# skydrop.net
KiCad netlist of a schematic drawn in EAGLE
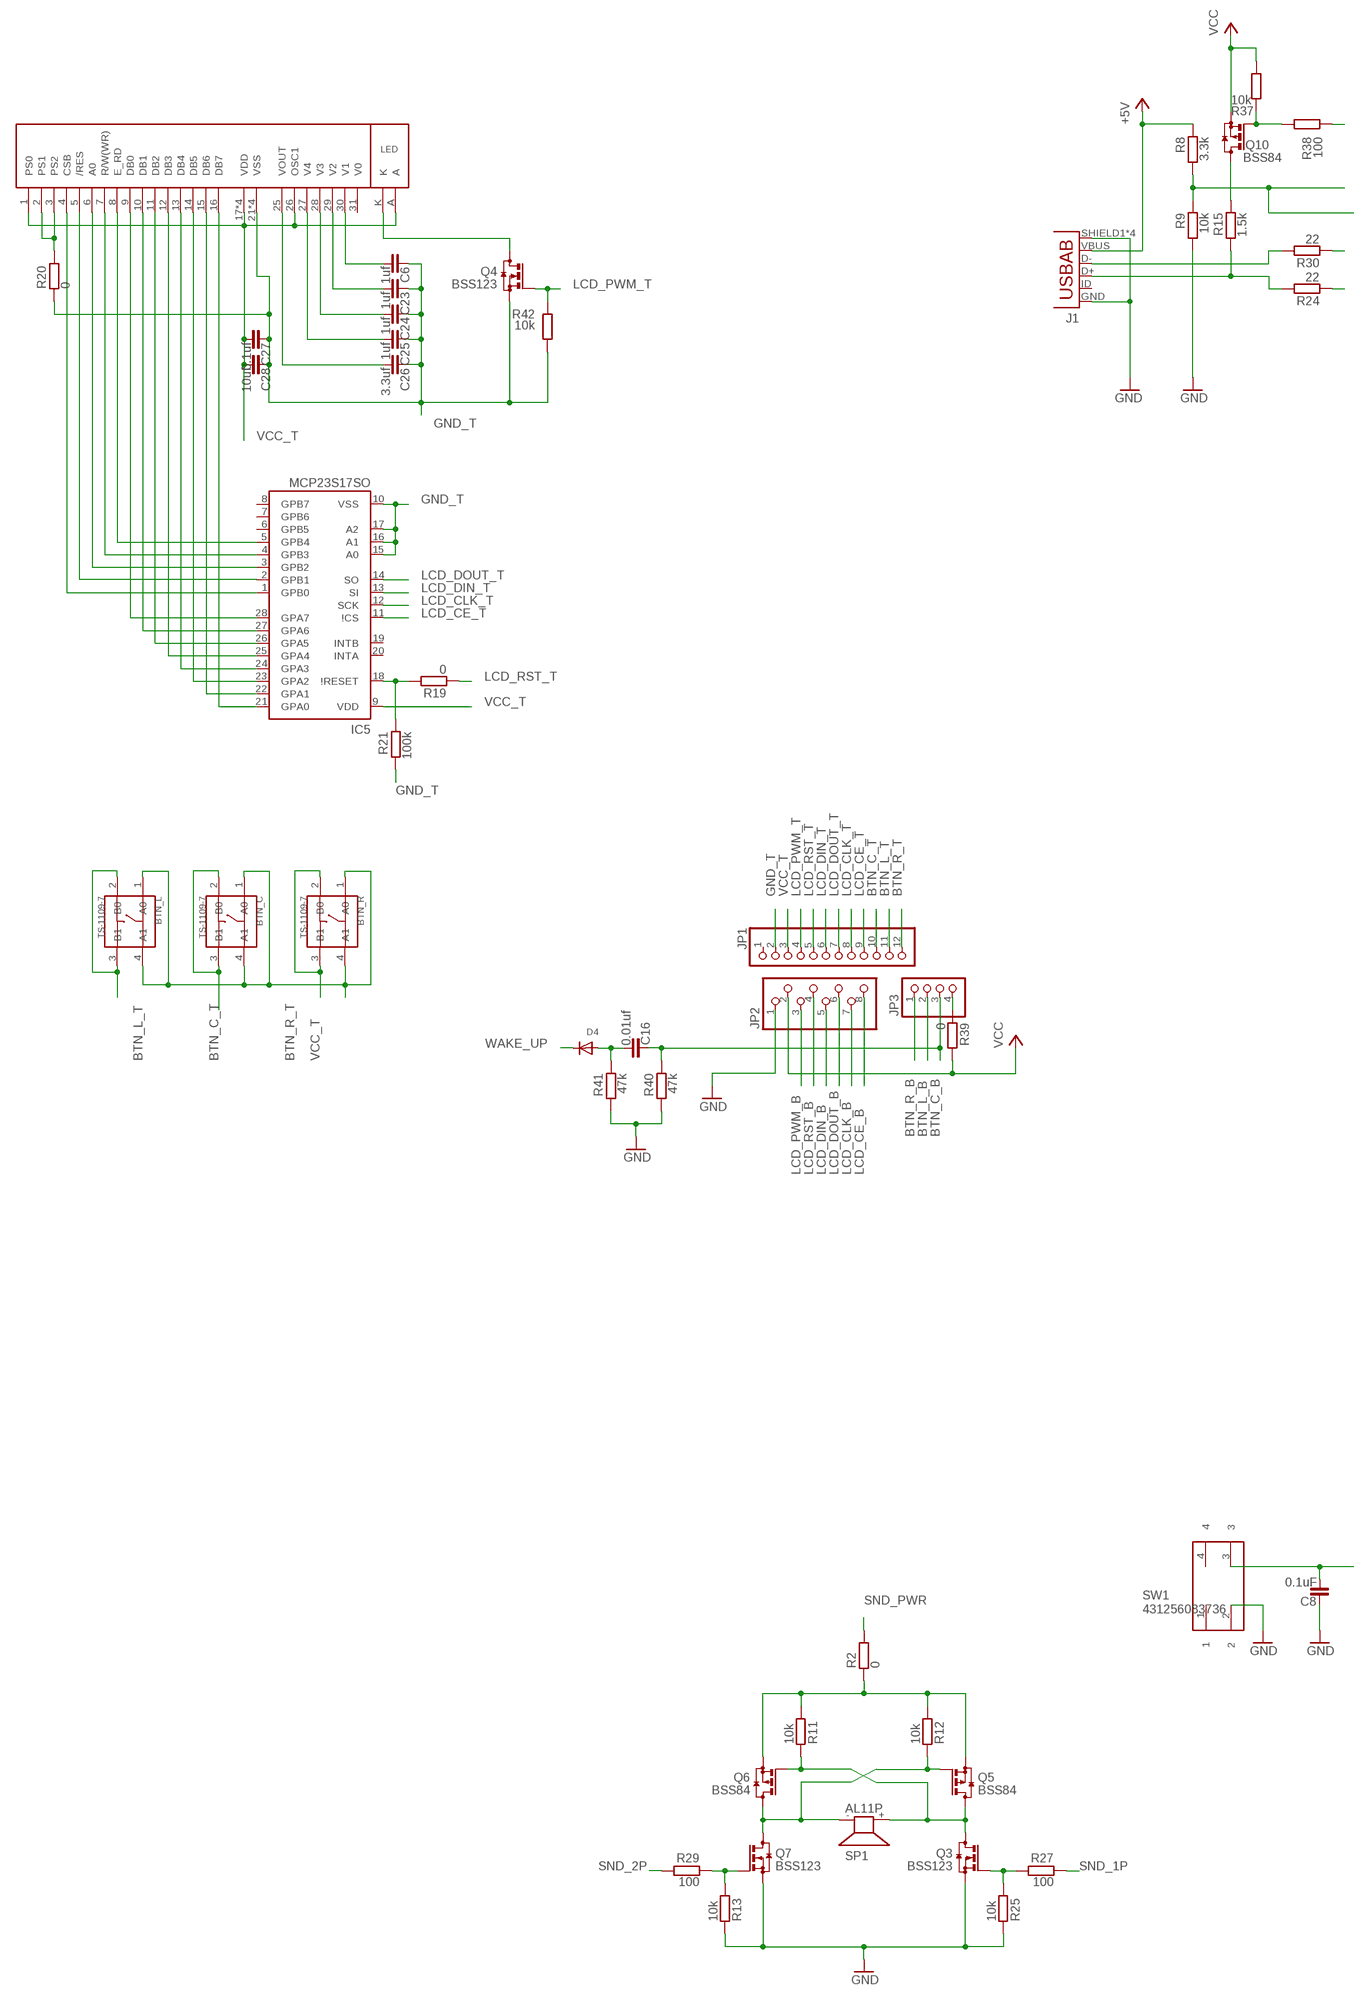
[diagram p0: schematic, sheet 1, part 1 of 2]
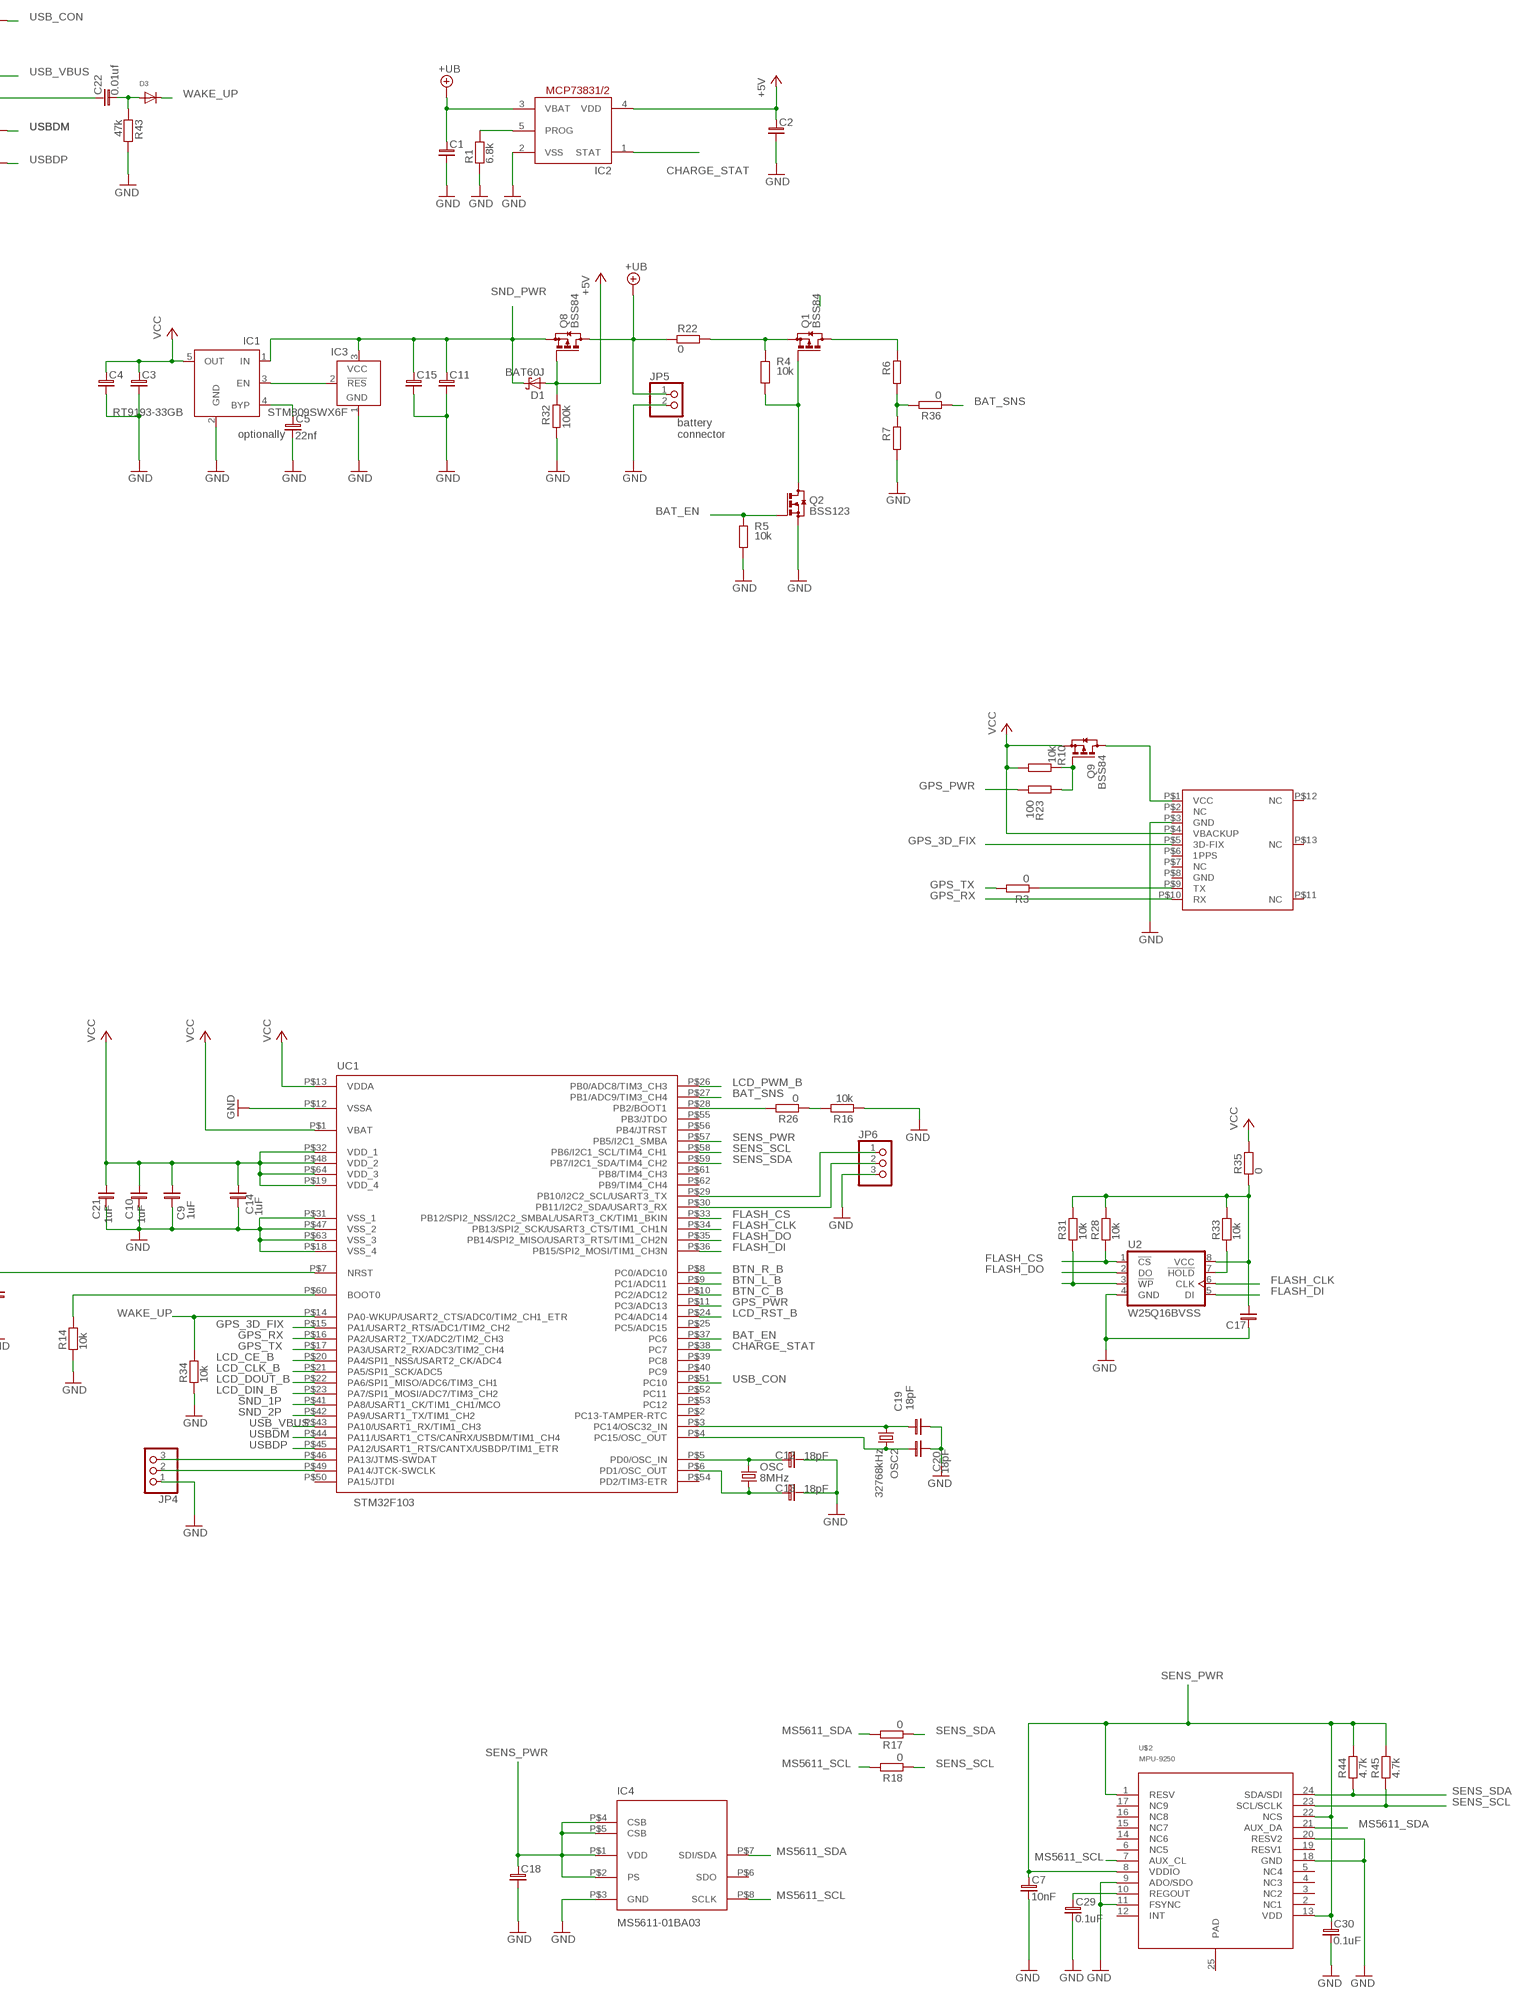
[diagram p1: schematic, sheet 1, part 2 of 2]

(export (version "E")
  (design (tool "Eeschema 10.0.6"))
  (components
    (comp (ref "BTN_C")
      (value "TS-1109-7")
      (footprint "eagle-import:SW4-6.2X6.2X5.0MM")
      (libsource (lib "eagle-import") (part "DIP-BUTTON-TOP-BLACK(4P-D6.2MM)"))
    )
    (comp (ref "BTN_L")
      (value "TS-1109-7")
      (footprint "eagle-import:SW4-6.2X6.2X5.0MM")
      (libsource (lib "eagle-import") (part "DIP-BUTTON-TOP-BLACK(4P-D6.2MM)"))
    )
    (comp (ref "BTN_R")
      (value "TS-1109-7")
      (footprint "eagle-import:SW4-6.2X6.2X5.0MM")
      (libsource (lib "eagle-import") (part "DIP-BUTTON-TOP-BLACK(4P-D6.2MM)"))
    )
    (comp (ref "C1")
      (value "C_0805")
      (footprint "eagle-import:C0805")
      (libsource (lib "eagle-import") (part "C_0805"))
    )
    (comp (ref "C2")
      (value "C_0805")
      (footprint "eagle-import:C0805")
      (libsource (lib "eagle-import") (part "C_0805"))
    )
    (comp (ref "C3")
      (value "C_0805")
      (footprint "eagle-import:C0805")
      (libsource (lib "eagle-import") (part "C_0805"))
    )
    (comp (ref "C4")
      (value "C_0805")
      (footprint "eagle-import:C0805")
      (libsource (lib "eagle-import") (part "C_0805"))
    )
    (comp (ref "C5")
      (value "22nf")
      (footprint "eagle-import:C0805")
      (libsource (lib "eagle-import") (part "C_0805"))
    )
    (comp (ref "C6")
      (value "1uf")
      (footprint "eagle-import:C0805")
      (libsource (lib "eagle-import") (part "C_0805"))
    )
    (comp (ref "C7")
      (value "10nF")
      (footprint "eagle-import:C0805")
      (libsource (lib "eagle-import") (part "C_0805"))
    )
    (comp (ref "C8")
      (value "0.1uF")
      (footprint "eagle-import:C0805")
      (libsource (lib "eagle-import") (part "C_0805"))
    )
    (comp (ref "C9")
      (value "1uF")
      (footprint "eagle-import:C0805")
      (libsource (lib "eagle-import") (part "C_0805"))
    )
    (comp (ref "C10")
      (value "1uF")
      (footprint "eagle-import:C0805")
      (libsource (lib "eagle-import") (part "C_0805"))
    )
    (comp (ref "C11")
      (value "C_0805")
      (footprint "eagle-import:C0805")
      (libsource (lib "eagle-import") (part "C_0805"))
    )
    (comp (ref "C12")
      (value "18pF")
      (footprint "eagle-import:C0805")
      (libsource (lib "eagle-import") (part "C_0805"))
    )
    (comp (ref "C13")
      (value "18pF")
      (footprint "eagle-import:C0805")
      (libsource (lib "eagle-import") (part "C_0805"))
    )
    (comp (ref "C14")
      (value "1uF")
      (footprint "eagle-import:C0805")
      (libsource (lib "eagle-import") (part "C_0805"))
    )
    (comp (ref "C15")
      (value "C_0805")
      (footprint "eagle-import:C0805")
      (libsource (lib "eagle-import") (part "C_0805"))
    )
    (comp (ref "C16")
      (value "0.01uf")
      (footprint "eagle-import:C0805")
      (libsource (lib "eagle-import") (part "C_0805"))
    )
    (comp (ref "C17")
      (value "C_0805")
      (footprint "eagle-import:C0805")
      (libsource (lib "eagle-import") (part "C_0805"))
    )
    (comp (ref "C18")
      (value "C_0805")
      (footprint "eagle-import:C0805")
      (libsource (lib "eagle-import") (part "C_0805"))
    )
    (comp (ref "C19")
      (value "18pF")
      (footprint "eagle-import:C0805")
      (libsource (lib "eagle-import") (part "C_0805"))
    )
    (comp (ref "C20")
      (value "18pF")
      (footprint "eagle-import:C0805")
      (libsource (lib "eagle-import") (part "C_0805"))
    )
    (comp (ref "C21")
      (value "1uF")
      (footprint "eagle-import:C0805")
      (libsource (lib "eagle-import") (part "C_0805"))
    )
    (comp (ref "C22")
      (value "0.01uf")
      (footprint "eagle-import:C0805")
      (libsource (lib "eagle-import") (part "C_0805"))
    )
    (comp (ref "C23")
      (value "1uf")
      (footprint "eagle-import:C0805")
      (libsource (lib "eagle-import") (part "C_0805"))
    )
    (comp (ref "C24")
      (value "1uf")
      (footprint "eagle-import:C0805")
      (libsource (lib "eagle-import") (part "C_0805"))
    )
    (comp (ref "C25")
      (value "1uf")
      (footprint "eagle-import:C0805")
      (libsource (lib "eagle-import") (part "C_0805"))
    )
    (comp (ref "C26")
      (value "3.3uf")
      (footprint "eagle-import:C0805")
      (libsource (lib "eagle-import") (part "C_0805"))
    )
    (comp (ref "C27")
      (value "0.1uf")
      (footprint "eagle-import:C0805")
      (libsource (lib "eagle-import") (part "C_0805"))
    )
    (comp (ref "C28")
      (value "10uf")
      (footprint "eagle-import:C0805")
      (libsource (lib "eagle-import") (part "C_0805"))
    )
    (comp (ref "C29")
      (value "0.1uF")
      (footprint "eagle-import:C0805")
      (libsource (lib "eagle-import") (part "C_0805"))
    )
    (comp (ref "C30")
      (value "0.1uF")
      (footprint "eagle-import:C0805")
      (libsource (lib "eagle-import") (part "C_0805"))
    )
    (comp (ref "D1")
      (value "BAT60J")
      (footprint "eagle-import:SOD323_ST")
      (libsource (lib "eagle-import") (part "BAT60J"))
    )
    (comp (ref "D3")
      (value "DIODE_SOD-123FL")
      (footprint "eagle-import:SOD-123FL")
      (libsource (lib "eagle-import") (part "DIODE_SOD-123FL"))
    )
    (comp (ref "D4")
      (value "DIODE_SOD-123FL")
      (footprint "eagle-import:SOD-123FL")
      (libsource (lib "eagle-import") (part "DIODE_SOD-123FL"))
    )
    (comp (ref "IC1")
      (value "RT9193-33GB")
      (footprint "eagle-import:SOT23-5")
      (libsource (lib "eagle-import") (part "MIC5219XX"))
    )
    (comp (ref "IC2")
      (value "MCP73831/OT")
      (footprint "eagle-import:SOT23-5L")
      (libsource (lib "eagle-import") (part "MCP73831/OT"))
    )
    (comp (ref "IC3")
      (value "STM809SWX6F")
      (footprint "eagle-import:SOT23B-3")
      (fields (field (name "MF") "MICROCHIP") (field (name "MPN") "TCM809MENB713"))
      (libsource (lib "eagle-import") (part "TCM809"))
    )
    (comp (ref "IC4")
      (value "MS5611-01BA03")
      (footprint "eagle-import:MS5611-01BA03")
      (libsource (lib "eagle-import") (part "MS5611-01BA03"))
    )
    (comp (ref "IC5")
      (value "MCP23S17SO")
      (footprint "eagle-import:SO28W")
      (libsource (lib "eagle-import") (part "MCP23S17SO"))
    )
    (comp (ref "J1")
      (value "USB-AB")
      (footprint "eagle-import:USB-AB-MICRO-SMD")
      (libsource (lib "eagle-import") (part "USB-AB"))
    )
    (comp (ref "JP1")
      (value "PINHD-1X12")
      (footprint "eagle-import:1X12")
      (libsource (lib "eagle-import") (part "PINHD-1X12"))
    )
    (comp (ref "JP2")
      (value "PINHD-1X8")
      (footprint "eagle-import:1X08")
      (libsource (lib "eagle-import") (part "PINHD-1X8"))
    )
    (comp (ref "JP3")
      (value "PINHD-1X4")
      (footprint "eagle-import:1X04")
      (libsource (lib "eagle-import") (part "PINHD-1X4"))
    )
    (comp (ref "JP4")
      (value "PINHD-1X3")
      (footprint "eagle-import:1X03")
      (libsource (lib "eagle-import") (part "PINHD-1X3"))
    )
    (comp (ref "JP5")
      (value "PINHD-1X2")
      (footprint "eagle-import:1X02")
      (libsource (lib "eagle-import") (part "PINHD-1X2"))
    )
    (comp (ref "JP6")
      (value "PINHD-1X3")
      (footprint "eagle-import:1X03")
      (libsource (lib "eagle-import") (part "PINHD-1X3"))
    )
    (comp (ref "OSC")
      (value "8MHz")
      (footprint "eagle-import:HC49_S")
      (libsource (lib "eagle-import") (part "CRYSTALHC49S"))
    )
    (comp (ref "OSC2")
      (value "32768kHz")
      (footprint "eagle-import:MM20SS")
      (libsource (lib "eagle-import") (part "CRYSTALMM20SS"))
    )
    (comp (ref "Q1")
      (value "BSS84")
      (footprint "eagle-import:SOT23")
      (libsource (lib "eagle-import") (part "BSS84"))
    )
    (comp (ref "Q2")
      (value "BSS123")
      (footprint "eagle-import:SOT23")
      (libsource (lib "eagle-import") (part "BSS123"))
    )
    (comp (ref "Q3")
      (value "BSS123")
      (footprint "eagle-import:SOT23")
      (libsource (lib "eagle-import") (part "BSS123"))
    )
    (comp (ref "Q4")
      (value "BSS123")
      (footprint "eagle-import:SOT23")
      (libsource (lib "eagle-import") (part "BSS123"))
    )
    (comp (ref "Q5")
      (value "BSS84")
      (footprint "eagle-import:SOT23")
      (libsource (lib "eagle-import") (part "BSS84"))
    )
    (comp (ref "Q6")
      (value "BSS84")
      (footprint "eagle-import:SOT23")
      (libsource (lib "eagle-import") (part "BSS84"))
    )
    (comp (ref "Q7")
      (value "BSS123")
      (footprint "eagle-import:SOT23")
      (libsource (lib "eagle-import") (part "BSS123"))
    )
    (comp (ref "Q8")
      (value "BSS84")
      (footprint "eagle-import:SOT23")
      (libsource (lib "eagle-import") (part "BSS84"))
    )
    (comp (ref "Q9")
      (value "BSS84")
      (footprint "eagle-import:SOT23")
      (libsource (lib "eagle-import") (part "BSS84"))
    )
    (comp (ref "Q10")
      (value "BSS84")
      (footprint "eagle-import:SOT23")
      (libsource (lib "eagle-import") (part "BSS84"))
    )
    (comp (ref "R1")
      (value "6.8k")
      (footprint "eagle-import:R0805")
      (libsource (lib "eagle-import") (part "R_0805"))
    )
    (comp (ref "R2")
      (value "0")
      (footprint "eagle-import:R1206")
      (libsource (lib "eagle-import") (part "R_1206"))
    )
    (comp (ref "R3")
      (value "0")
      (footprint "eagle-import:R1206")
      (libsource (lib "eagle-import") (part "R_1206"))
    )
    (comp (ref "R4")
      (value "10k")
      (footprint "eagle-import:R0805")
      (libsource (lib "eagle-import") (part "R_0805"))
    )
    (comp (ref "R5")
      (value "10k")
      (footprint "eagle-import:R0805")
      (libsource (lib "eagle-import") (part "R_0805"))
    )
    (comp (ref "R6")
      (value "R_0805")
      (footprint "eagle-import:R0805")
      (libsource (lib "eagle-import") (part "R_0805"))
    )
    (comp (ref "R7")
      (value "R_0805")
      (footprint "eagle-import:R0805")
      (libsource (lib "eagle-import") (part "R_0805"))
    )
    (comp (ref "R8")
      (value "3.3k")
      (footprint "eagle-import:R0805")
      (libsource (lib "eagle-import") (part "R_0805"))
    )
    (comp (ref "R9")
      (value "10k")
      (footprint "eagle-import:R0805")
      (libsource (lib "eagle-import") (part "R_0805"))
    )
    (comp (ref "R10")
      (value "10k")
      (footprint "eagle-import:R0805")
      (libsource (lib "eagle-import") (part "R_0805"))
    )
    (comp (ref "R11")
      (value "10k")
      (footprint "eagle-import:R0805")
      (libsource (lib "eagle-import") (part "R_0805"))
    )
    (comp (ref "R12")
      (value "10k")
      (footprint "eagle-import:R0805")
      (libsource (lib "eagle-import") (part "R_0805"))
    )
    (comp (ref "R13")
      (value "10k")
      (footprint "eagle-import:R0805")
      (libsource (lib "eagle-import") (part "R_0805"))
    )
    (comp (ref "R14")
      (value "10k")
      (footprint "eagle-import:R0805")
      (libsource (lib "eagle-import") (part "R_0805"))
    )
    (comp (ref "R15")
      (value "1.5k")
      (footprint "eagle-import:R0805")
      (libsource (lib "eagle-import") (part "R_0805"))
    )
    (comp (ref "R16")
      (value "10k")
      (footprint "eagle-import:R0805")
      (libsource (lib "eagle-import") (part "R_0805"))
    )
    (comp (ref "R17")
      (value "0")
      (footprint "eagle-import:R1206")
      (libsource (lib "eagle-import") (part "R_1206"))
    )
    (comp (ref "R18")
      (value "0")
      (footprint "eagle-import:R1206")
      (libsource (lib "eagle-import") (part "R_1206"))
    )
    (comp (ref "R19")
      (value "0")
      (footprint "eagle-import:R1206")
      (libsource (lib "eagle-import") (part "R_1206"))
    )
    (comp (ref "R20")
      (value "0")
      (footprint "eagle-import:R1206")
      (libsource (lib "eagle-import") (part "R_1206"))
    )
    (comp (ref "R21")
      (value "100k")
      (footprint "eagle-import:R0805")
      (libsource (lib "eagle-import") (part "R_0805"))
    )
    (comp (ref "R22")
      (value "0")
      (footprint "eagle-import:R1206")
      (libsource (lib "eagle-import") (part "R_1206"))
    )
    (comp (ref "R23")
      (value "100")
      (footprint "eagle-import:R0805")
      (libsource (lib "eagle-import") (part "R_0805"))
    )
    (comp (ref "R24")
      (value "22")
      (footprint "eagle-import:R0805")
      (libsource (lib "eagle-import") (part "R_0805"))
    )
    (comp (ref "R25")
      (value "10k")
      (footprint "eagle-import:R0805")
      (libsource (lib "eagle-import") (part "R_0805"))
    )
    (comp (ref "R26")
      (value "0")
      (footprint "eagle-import:R1206")
      (libsource (lib "eagle-import") (part "R_1206"))
    )
    (comp (ref "R27")
      (value "100")
      (footprint "eagle-import:R0805")
      (libsource (lib "eagle-import") (part "R_0805"))
    )
    (comp (ref "R28")
      (value "10k")
      (footprint "eagle-import:R0805")
      (libsource (lib "eagle-import") (part "R_0805"))
    )
    (comp (ref "R29")
      (value "100")
      (footprint "eagle-import:R0805")
      (libsource (lib "eagle-import") (part "R_0805"))
    )
    (comp (ref "R30")
      (value "22")
      (footprint "eagle-import:R0805")
      (libsource (lib "eagle-import") (part "R_0805"))
    )
    (comp (ref "R31")
      (value "10k")
      (footprint "eagle-import:R0805")
      (libsource (lib "eagle-import") (part "R_0805"))
    )
    (comp (ref "R32")
      (value "100k")
      (footprint "eagle-import:R0805")
      (libsource (lib "eagle-import") (part "R_0805"))
    )
    (comp (ref "R33")
      (value "10k")
      (footprint "eagle-import:R0805")
      (libsource (lib "eagle-import") (part "R_0805"))
    )
    (comp (ref "R34")
      (value "10k")
      (footprint "eagle-import:R0805")
      (libsource (lib "eagle-import") (part "R_0805"))
    )
    (comp (ref "R35")
      (value "0")
      (footprint "eagle-import:R1206")
      (libsource (lib "eagle-import") (part "R_1206"))
    )
    (comp (ref "R36")
      (value "0")
      (footprint "eagle-import:R1206")
      (libsource (lib "eagle-import") (part "R_1206"))
    )
    (comp (ref "R37")
      (value "10k")
      (footprint "eagle-import:R0805")
      (libsource (lib "eagle-import") (part "R_0805"))
    )
    (comp (ref "R38")
      (value "100")
      (footprint "eagle-import:R0805")
      (libsource (lib "eagle-import") (part "R_0805"))
    )
    (comp (ref "R39")
      (value "0")
      (footprint "eagle-import:R1206")
      (libsource (lib "eagle-import") (part "R_1206"))
    )
    (comp (ref "R40")
      (value "47k")
      (footprint "eagle-import:R0805")
      (libsource (lib "eagle-import") (part "R_0805"))
    )
    (comp (ref "R41")
      (value "47k")
      (footprint "eagle-import:R0805")
      (libsource (lib "eagle-import") (part "R_0805"))
    )
    (comp (ref "R42")
      (value "10k")
      (footprint "eagle-import:R0805")
      (libsource (lib "eagle-import") (part "R_0805"))
    )
    (comp (ref "R43")
      (value "47k")
      (footprint "eagle-import:R0805")
      (libsource (lib "eagle-import") (part "R_0805"))
    )
    (comp (ref "R44")
      (value "4.7k")
      (footprint "eagle-import:R0805")
      (libsource (lib "eagle-import") (part "R_0805"))
    )
    (comp (ref "R45")
      (value "4.7k")
      (footprint "eagle-import:R0805")
      (libsource (lib "eagle-import") (part "R_0805"))
    )
    (comp (ref "SP1")
      (value "AL11P")
      (footprint "eagle-import:AL11P")
      (libsource (lib "eagle-import") (part "AL11P"))
    )
    (comp (ref "SW1")
      (value "431256083736")
      (footprint "eagle-import:431256083736")
      (libsource (lib "eagle-import") (part "431256083736"))
    )
    (comp (ref "U$1")
      (value "NOKIA5110")
      (footprint "eagle-import:NOKIA5110")
      (libsource (lib "eagle-import") (part "NOKIA5110"))
    )
    (comp (ref "U$2")
      (value "MPU-9250")
      (footprint "eagle-import:LEAD-QFN24")
      (libsource (lib "eagle-import") (part "MPU-9250"))
    )
    (comp (ref "U1")
      (value "GPS_FGPMMOPA6C")
      (footprint "eagle-import:FGPMMOPA6C")
      (libsource (lib "eagle-import") (part "GPS_FGPMMOPA6C"))
    )
    (comp (ref "U2")
      (value "W25Q16BVSS")
      (footprint "eagle-import:SO08-SS")
      (libsource (lib "eagle-import") (part "W25Q16BVSS"))
    )
    (comp (ref "UC1")
      (value "STM32F103")
      (footprint "eagle-import:TQFP-10X10-64")
      (libsource (lib "eagle-import") (part "STM32F103"))
    )
  )
  (nets
    (net (code "1") (name "+5V") (class "Default")
      (node (ref "C2") (pin "1") (pinfunction "1_1") (pintype "passive"))
      (node (ref "D1") (pin "A") (pinfunction "A_A") (pintype "passive"))
      (node (ref "IC2") (pin "4") (pinfunction "VDD_4") (pintype "power_in"))
      (node (ref "J1") (pin "VBUS") (pinfunction "VBUS_VBUS") (pintype "bidirectional"))
      (node (ref "Q8") (pin "1") (pinfunction "G_1") (pintype "passive"))
      (node (ref "R32") (pin "1") (pinfunction "1_1") (pintype "passive"))
      (node (ref "R8") (pin "1") (pinfunction "1_1") (pintype "passive"))
    )
    (net (code "2") (name "+UB") (class "Default")
      (node (ref "C1") (pin "1") (pinfunction "1_1") (pintype "passive"))
      (node (ref "IC2") (pin "3") (pinfunction "VBAT_3") (pintype "bidirectional"))
      (node (ref "JP5") (pin "1") (pinfunction "1_1") (pintype "passive"))
      (node (ref "Q8") (pin "3") (pinfunction "D_3") (pintype "passive"))
      (node (ref "R22") (pin "1") (pinfunction "1_1") (pintype "passive"))
    )
    (net (code "3") (name "/BAT_EN") (class "Default")
      (node (ref "Q2") (pin "1") (pinfunction "G_1") (pintype "passive"))
      (node (ref "R5") (pin "1") (pinfunction "1_1") (pintype "passive"))
      (node (ref "UC1") (pin "P$37") (pinfunction "PC6_P$37") (pintype "bidirectional"))
    )
    (net (code "4") (name "/BAT_SNS") (class "Default")
      (node (ref "R36") (pin "1") (pinfunction "1_1") (pintype "passive"))
      (node (ref "UC1") (pin "P$27") (pinfunction "PB1/ADC9/TIM3_CH4_P$27") (pintype "bidirectional"))
    )
    (net (code "5") (name "/BTN_C_B") (class "Default")
      (node (ref "C16") (pin "1") (pinfunction "1_1") (pintype "passive"))
      (node (ref "JP3") (pin "3") (pinfunction "3_3") (pintype "passive"))
      (node (ref "R40") (pin "1") (pinfunction "1_1") (pintype "passive"))
      (node (ref "UC1") (pin "P$10") (pinfunction "PC2/ADC12_P$10") (pintype "bidirectional"))
    )
    (net (code "6") (name "/BTN_C_T") (class "Default")
      (node (ref "BTN_C") (pin "2") (pinfunction "B0_2") (pintype "bidirectional"))
      (node (ref "BTN_C") (pin "3") (pinfunction "B1_3") (pintype "bidirectional"))
      (node (ref "JP1") (pin "10") (pinfunction "10_10") (pintype "passive"))
    )
    (net (code "7") (name "/BTN_L_B") (class "Default")
      (node (ref "JP3") (pin "2") (pinfunction "2_2") (pintype "passive"))
      (node (ref "UC1") (pin "P$9") (pinfunction "PC1/ADC11_P$9") (pintype "bidirectional"))
    )
    (net (code "8") (name "/BTN_L_T") (class "Default")
      (node (ref "BTN_L") (pin "2") (pinfunction "B0_2") (pintype "bidirectional"))
      (node (ref "BTN_L") (pin "3") (pinfunction "B1_3") (pintype "bidirectional"))
      (node (ref "JP1") (pin "11") (pinfunction "11_11") (pintype "passive"))
    )
    (net (code "9") (name "/BTN_R_B") (class "Default")
      (node (ref "JP3") (pin "1") (pinfunction "1_1") (pintype "passive"))
      (node (ref "UC1") (pin "P$8") (pinfunction "PC0/ADC10_P$8") (pintype "bidirectional"))
    )
    (net (code "10") (name "/BTN_R_T") (class "Default")
      (node (ref "BTN_R") (pin "2") (pinfunction "B0_2") (pintype "bidirectional"))
      (node (ref "BTN_R") (pin "3") (pinfunction "B1_3") (pintype "bidirectional"))
      (node (ref "JP1") (pin "12") (pinfunction "12_12") (pintype "passive"))
    )
    (net (code "11") (name "/CHARGE_STAT") (class "Default")
      (node (ref "IC2") (pin "1") (pinfunction "STAT_1") (pintype "output"))
      (node (ref "UC1") (pin "P$38") (pinfunction "PC7_P$38") (pintype "bidirectional"))
    )
    (net (code "12") (name "/FLASH_CLK") (class "Default")
      (node (ref "U2") (pin "6") (pinfunction "CLK_6") (pintype "input"))
      (node (ref "UC1") (pin "P$34") (pinfunction "PB13/SPI2_SCK/USART3_CTS/TIM1_CH1N_P$34") (pintype "bidirectional"))
    )
    (net (code "13") (name "/FLASH_CS") (class "Default")
      (node (ref "R28") (pin "1") (pinfunction "1_1") (pintype "passive"))
      (node (ref "U2") (pin "1") (pinfunction "~{CS}_1") (pintype "input"))
      (node (ref "UC1") (pin "P$33") (pinfunction "PB12/SPI2_NSS/I2C2_SMBAL/USART3_CK/TIM1_BKIN_P$33") (pintype "bidirectional"))
    )
    (net (code "14") (name "/FLASH_DI") (class "Default")
      (node (ref "U2") (pin "5") (pinfunction "DI_5") (pintype "input"))
      (node (ref "UC1") (pin "P$36") (pinfunction "PB15/SPI2_MOSI/TIM1_CH3N_P$36") (pintype "bidirectional"))
    )
    (net (code "15") (name "/FLASH_DO") (class "Default")
      (node (ref "U2") (pin "2") (pinfunction "DO_2") (pintype "output"))
      (node (ref "UC1") (pin "P$35") (pinfunction "PB14/SPI2_MISO/USART3_RTS/TIM1_CH2N_P$35") (pintype "bidirectional"))
    )
    (net (code "16") (name "/GND_T") (class "Default")
      (node (ref "C23") (pin "1") (pinfunction "1_1") (pintype "passive"))
      (node (ref "C24") (pin "1") (pinfunction "1_1") (pintype "passive"))
      (node (ref "C25") (pin "1") (pinfunction "1_1") (pintype "passive"))
      (node (ref "C26") (pin "1") (pinfunction "1_1") (pintype "passive"))
      (node (ref "C27") (pin "1") (pinfunction "1_1") (pintype "passive"))
      (node (ref "C28") (pin "1") (pinfunction "1_1") (pintype "passive"))
      (node (ref "C6") (pin "1") (pinfunction "1_1") (pintype "passive"))
      (node (ref "IC5") (pin "10") (pinfunction "VSS_10") (pintype "power_in"))
      (node (ref "IC5") (pin "15") (pinfunction "A0_15") (pintype "input"))
      (node (ref "IC5") (pin "16") (pinfunction "A1_16") (pintype "input"))
      (node (ref "IC5") (pin "17") (pinfunction "A2_17") (pintype "input"))
      (node (ref "JP1") (pin "2") (pinfunction "2_2") (pintype "passive"))
      (node (ref "Q4") (pin "2") (pinfunction "S_2") (pintype "passive"))
      (node (ref "R20") (pin "1") (pinfunction "1_1") (pintype "passive"))
      (node (ref "R21") (pin "2") (pinfunction "2_2") (pintype "passive"))
      (node (ref "R42") (pin "2") (pinfunction "2_2") (pintype "passive"))
      (node (ref "U$1") (pin "21") (pinfunction "VSS_21") (pintype "bidirectional"))
      (node (ref "U$1") (pin "22") (pinfunction "VSS_22") (pintype "bidirectional"))
      (node (ref "U$1") (pin "23") (pinfunction "VSS_23") (pintype "bidirectional"))
      (node (ref "U$1") (pin "24") (pinfunction "VSS_24") (pintype "bidirectional"))
    )
    (net (code "17") (name "/GPS_3D_FIX") (class "Default")
      (node (ref "U1") (pin "P$5") (pinfunction "3D-FIX_P$5") (pintype "bidirectional"))
      (node (ref "UC1") (pin "P$15") (pinfunction "PA1/USART2_RTS/ADC1/TIM2_CH2_P$15") (pintype "bidirectional"))
    )
    (net (code "18") (name "/GPS_PWR") (class "Default")
      (node (ref "R23") (pin "2") (pinfunction "2_2") (pintype "passive"))
      (node (ref "UC1") (pin "P$11") (pinfunction "PC3/ADC13_P$11") (pintype "bidirectional"))
    )
    (net (code "19") (name "/GPS_RX") (class "Default")
      (node (ref "U1") (pin "P$10") (pinfunction "RX_P$10") (pintype "bidirectional"))
      (node (ref "UC1") (pin "P$16") (pinfunction "PA2/USART2_TX/ADC2/TIM2_CH3_P$16") (pintype "bidirectional"))
    )
    (net (code "20") (name "/GPS_TX") (class "Default")
      (node (ref "R3") (pin "2") (pinfunction "2_2") (pintype "passive"))
      (node (ref "UC1") (pin "P$17") (pinfunction "PA3/USART2_RX/ADC3/TIM2_CH4_P$17") (pintype "bidirectional"))
    )
    (net (code "21") (name "/LCD_CE_B") (class "Default")
      (node (ref "JP2") (pin "8") (pinfunction "8_8") (pintype "passive"))
      (node (ref "UC1") (pin "P$20") (pinfunction "PA4/SPI1_NSS/USART2_CK/ADC4_P$20") (pintype "bidirectional"))
    )
    (net (code "22") (name "/LCD_CE_T") (class "Default")
      (node (ref "IC5") (pin "11") (pinfunction "\\~{CS}_11") (pintype "input"))
      (node (ref "JP1") (pin "9") (pinfunction "9_9") (pintype "passive"))
    )
    (net (code "23") (name "/LCD_CLK_B") (class "Default")
      (node (ref "JP2") (pin "7") (pinfunction "7_7") (pintype "passive"))
      (node (ref "UC1") (pin "P$21") (pinfunction "PA5/SPI1_SCK/ADC5_P$21") (pintype "bidirectional"))
    )
    (net (code "24") (name "/LCD_CLK_T") (class "Default")
      (node (ref "IC5") (pin "12") (pinfunction "SCK_12") (pintype "input"))
      (node (ref "JP1") (pin "8") (pinfunction "8_8") (pintype "passive"))
    )
    (net (code "25") (name "/LCD_DIN_B") (class "Default")
      (node (ref "JP2") (pin "5") (pinfunction "5_5") (pintype "passive"))
      (node (ref "UC1") (pin "P$23") (pinfunction "PA7/SPI1_MOSI/ADC7/TIM3_CH2_P$23") (pintype "bidirectional"))
    )
    (net (code "26") (name "/LCD_DIN_T") (class "Default")
      (node (ref "IC5") (pin "13") (pinfunction "SI_13") (pintype "input"))
      (node (ref "JP1") (pin "6") (pinfunction "6_6") (pintype "passive"))
    )
    (net (code "27") (name "/LCD_DOUT_B") (class "Default")
      (node (ref "JP2") (pin "6") (pinfunction "6_6") (pintype "passive"))
      (node (ref "UC1") (pin "P$22") (pinfunction "PA6/SPI1_MISO/ADC6/TIM3_CH1_P$22") (pintype "bidirectional"))
    )
    (net (code "28") (name "/LCD_DOUT_T") (class "Default")
      (node (ref "IC5") (pin "14") (pinfunction "SO_14") (pintype "output"))
      (node (ref "JP1") (pin "7") (pinfunction "7_7") (pintype "passive"))
    )
    (net (code "29") (name "/LCD_PWM_B") (class "Default")
      (node (ref "JP2") (pin "3") (pinfunction "3_3") (pintype "passive"))
      (node (ref "UC1") (pin "P$26") (pinfunction "PB0/ADC8/TIM3_CH3_P$26") (pintype "bidirectional"))
    )
    (net (code "30") (name "/LCD_PWM_T") (class "Default")
      (node (ref "JP1") (pin "4") (pinfunction "4_4") (pintype "passive"))
      (node (ref "Q4") (pin "1") (pinfunction "G_1") (pintype "passive"))
      (node (ref "R42") (pin "1") (pinfunction "1_1") (pintype "passive"))
    )
    (net (code "31") (name "/LCD_RST_B") (class "Default")
      (node (ref "JP2") (pin "4") (pinfunction "4_4") (pintype "passive"))
      (node (ref "UC1") (pin "P$24") (pinfunction "PC4/ADC14_P$24") (pintype "bidirectional"))
    )
    (net (code "32") (name "/LCD_RST_T") (class "Default")
      (node (ref "JP1") (pin "5") (pinfunction "5_5") (pintype "passive"))
      (node (ref "R19") (pin "1") (pinfunction "1_1") (pintype "passive"))
    )
    (net (code "33") (name "/MS5611_SCL") (class "Default")
      (node (ref "IC4") (pin "P$8") (pinfunction "SCLK_P$8") (pintype "input"))
      (node (ref "R18") (pin "2") (pinfunction "2_2") (pintype "passive"))
      (node (ref "U$2") (pin "7") (pinfunction "AUX_CL_7") (pintype "bidirectional"))
    )
    (net (code "34") (name "/MS5611_SDA") (class "Default")
      (node (ref "IC4") (pin "P$7") (pinfunction "SDI/SDA_P$7") (pintype "bidirectional"))
      (node (ref "R17") (pin "2") (pinfunction "2_2") (pintype "passive"))
      (node (ref "U$2") (pin "21") (pinfunction "AUX_DA_21") (pintype "bidirectional"))
    )
    (net (code "35") (name "/SENS_PWR") (class "Default")
      (node (ref "C18") (pin "1") (pinfunction "1_1") (pintype "passive"))
      (node (ref "C30") (pin "1") (pinfunction "1_1") (pintype "passive"))
      (node (ref "C7") (pin "1") (pinfunction "1_1") (pintype "passive"))
      (node (ref "IC4") (pin "P$1") (pinfunction "VDD_P$1") (pintype "power_in"))
      (node (ref "IC4") (pin "P$2") (pinfunction "PS_P$2") (pintype "input"))
      (node (ref "IC4") (pin "P$4") (pinfunction "CSB_P$4") (pintype "input"))
      (node (ref "IC4") (pin "P$5") (pinfunction "CSB_P$5") (pintype "input"))
      (node (ref "R44") (pin "2") (pinfunction "2_2") (pintype "passive"))
      (node (ref "R45") (pin "2") (pinfunction "2_2") (pintype "passive"))
      (node (ref "U$2") (pin "1") (pinfunction "RESV_1") (pintype "bidirectional"))
      (node (ref "U$2") (pin "13") (pinfunction "VDD_13") (pintype "bidirectional"))
      (node (ref "U$2") (pin "22") (pinfunction "NCS_22") (pintype "bidirectional"))
      (node (ref "U$2") (pin "8") (pinfunction "VDDIO_8") (pintype "bidirectional"))
      (node (ref "UC1") (pin "P$57") (pinfunction "PB5/I2C1_SMBA_P$57") (pintype "bidirectional"))
    )
    (net (code "36") (name "/SENS_SCL") (class "Default")
      (node (ref "R18") (pin "1") (pinfunction "1_1") (pintype "passive"))
      (node (ref "R45") (pin "1") (pinfunction "1_1") (pintype "passive"))
      (node (ref "U$2") (pin "23") (pinfunction "SCL/SCLK_23") (pintype "bidirectional"))
      (node (ref "UC1") (pin "P$58") (pinfunction "PB6/I2C1_SCL/TIM4_CH1_P$58") (pintype "bidirectional"))
    )
    (net (code "37") (name "/SENS_SDA") (class "Default")
      (node (ref "R17") (pin "1") (pinfunction "1_1") (pintype "passive"))
      (node (ref "R44") (pin "1") (pinfunction "1_1") (pintype "passive"))
      (node (ref "U$2") (pin "24") (pinfunction "SDA/SDI_24") (pintype "bidirectional"))
      (node (ref "UC1") (pin "P$59") (pinfunction "PB7/I2C1_SDA/TIM4_CH2_P$59") (pintype "bidirectional"))
    )
    (net (code "38") (name "/SND_1P") (class "Default")
      (node (ref "R27") (pin "1") (pinfunction "1_1") (pintype "passive"))
      (node (ref "UC1") (pin "P$41") (pinfunction "PA8/USART1_CK/TIM1_CH1/MCO_P$41") (pintype "bidirectional"))
    )
    (net (code "39") (name "/SND_2P") (class "Default")
      (node (ref "R29") (pin "2") (pinfunction "2_2") (pintype "passive"))
      (node (ref "UC1") (pin "P$42") (pinfunction "PA9/USART1_TX/TIM1_CH2_P$42") (pintype "bidirectional"))
    )
    (net (code "40") (name "/SND_PWR") (class "Default")
      (node (ref "C11") (pin "1") (pinfunction "1_1") (pintype "passive"))
      (node (ref "C15") (pin "1") (pinfunction "1_1") (pintype "passive"))
      (node (ref "D1") (pin "C") (pinfunction "C_C") (pintype "passive"))
      (node (ref "IC1") (pin "1") (pinfunction "IN_1") (pintype "input"))
      (node (ref "IC3") (pin "3") (pinfunction "VCC_3") (pintype "power_in"))
      (node (ref "Q8") (pin "2") (pinfunction "S_2") (pintype "passive"))
      (node (ref "R2") (pin "2") (pinfunction "2_2") (pintype "passive"))
    )
    (net (code "41") (name "/USBDM") (class "Default")
      (node (ref "R30") (pin "1") (pinfunction "1_1") (pintype "passive"))
      (node (ref "UC1") (pin "P$44") (pinfunction "PA11/USART1_CTS/CANRX/USBDM/TIM1_CH4_P$44") (pintype "bidirectional"))
    )
    (net (code "42") (name "/USBDP") (class "Default")
      (node (ref "R24") (pin "1") (pinfunction "1_1") (pintype "passive"))
      (node (ref "UC1") (pin "P$45") (pinfunction "PA12/USART1_RTS/CANTX/USBDP/TIM1_ETR_P$45") (pintype "bidirectional"))
    )
    (net (code "43") (name "/USB_CON") (class "Default")
      (node (ref "R38") (pin "2") (pinfunction "2_2") (pintype "passive"))
      (node (ref "UC1") (pin "P$51") (pinfunction "PC10_P$51") (pintype "bidirectional"))
    )
    (net (code "44") (name "/USB_VBUS") (class "Default")
      (node (ref "C22") (pin "1") (pinfunction "1_1") (pintype "passive"))
      (node (ref "R8") (pin "2") (pinfunction "2_2") (pintype "passive"))
      (node (ref "R9") (pin "1") (pinfunction "1_1") (pintype "passive"))
      (node (ref "UC1") (pin "P$43") (pinfunction "PA10/USART1_RX/TIM1_CH3_P$43") (pintype "bidirectional"))
    )
    (net (code "45") (name "/VCC_T") (class "Default")
      (node (ref "BTN_C") (pin "1") (pinfunction "A0_1") (pintype "bidirectional"))
      (node (ref "BTN_C") (pin "4") (pinfunction "A1_4") (pintype "bidirectional"))
      (node (ref "BTN_L") (pin "1") (pinfunction "A0_1") (pintype "bidirectional"))
      (node (ref "BTN_L") (pin "4") (pinfunction "A1_4") (pintype "bidirectional"))
      (node (ref "BTN_R") (pin "1") (pinfunction "A0_1") (pintype "bidirectional"))
      (node (ref "BTN_R") (pin "4") (pinfunction "A1_4") (pintype "bidirectional"))
      (node (ref "C27") (pin "2") (pinfunction "2_2") (pintype "passive"))
      (node (ref "C28") (pin "2") (pinfunction "2_2") (pintype "passive"))
      (node (ref "IC5") (pin "9") (pinfunction "VDD_9") (pintype "power_in"))
      (node (ref "JP1") (pin "3") (pinfunction "3_3") (pintype "passive"))
      (node (ref "U$1") (pin "1") (pinfunction "PS0_1") (pintype "bidirectional"))
      (node (ref "U$1") (pin "17") (pinfunction "VDD_17") (pintype "bidirectional"))
      (node (ref "U$1") (pin "18") (pinfunction "VDD_18") (pintype "bidirectional"))
      (node (ref "U$1") (pin "19") (pinfunction "VDD_19") (pintype "bidirectional"))
      (node (ref "U$1") (pin "20") (pinfunction "VDD_20") (pintype "bidirectional"))
      (node (ref "U$1") (pin "26") (pinfunction "OSC1_26") (pintype "bidirectional"))
      (node (ref "U$1") (pin "A") (pinfunction "A_A") (pintype "bidirectional"))
    )
    (net (code "46") (name "/WAKE_UP") (class "Default")
      (node (ref "D3") (pin "C") (pinfunction "C_C") (pintype "passive"))
      (node (ref "D4") (pin "C") (pinfunction "C_C") (pintype "passive"))
      (node (ref "R34") (pin "2") (pinfunction "2_2") (pintype "passive"))
      (node (ref "UC1") (pin "P$14") (pinfunction "PA0-WKUP/USART2_CTS/ADC0/TIM2_CH1_ETR_P$14") (pintype "bidirectional"))
    )
    (net (code "47") (name "GND") (class "Default")
      (node (ref "C1") (pin "2") (pinfunction "2_2") (pintype "passive"))
      (node (ref "C10") (pin "1") (pinfunction "1_1") (pintype "passive"))
      (node (ref "C11") (pin "2") (pinfunction "2_2") (pintype "passive"))
      (node (ref "C12") (pin "1") (pinfunction "1_1") (pintype "passive"))
      (node (ref "C13") (pin "1") (pinfunction "1_1") (pintype "passive"))
      (node (ref "C14") (pin "1") (pinfunction "1_1") (pintype "passive"))
      (node (ref "C15") (pin "2") (pinfunction "2_2") (pintype "passive"))
      (node (ref "C17") (pin "1") (pinfunction "1_1") (pintype "passive"))
      (node (ref "C18") (pin "2") (pinfunction "2_2") (pintype "passive"))
      (node (ref "C19") (pin "1") (pinfunction "1_1") (pintype "passive"))
      (node (ref "C2") (pin "2") (pinfunction "2_2") (pintype "passive"))
      (node (ref "C20") (pin "1") (pinfunction "1_1") (pintype "passive"))
      (node (ref "C21") (pin "1") (pinfunction "1_1") (pintype "passive"))
      (node (ref "C29") (pin "2") (pinfunction "2_2") (pintype "passive"))
      (node (ref "C3") (pin "2") (pinfunction "2_2") (pintype "passive"))
      (node (ref "C30") (pin "2") (pinfunction "2_2") (pintype "passive"))
      (node (ref "C4") (pin "2") (pinfunction "2_2") (pintype "passive"))
      (node (ref "C5") (pin "2") (pinfunction "2_2") (pintype "passive"))
      (node (ref "C7") (pin "2") (pinfunction "2_2") (pintype "passive"))
      (node (ref "C8") (pin "1") (pinfunction "1_1") (pintype "passive"))
      (node (ref "C9") (pin "1") (pinfunction "1_1") (pintype "passive"))
      (node (ref "IC1") (pin "2") (pinfunction "GND_2") (pintype "power_in"))
      (node (ref "IC2") (pin "2") (pinfunction "VSS_2") (pintype "power_in"))
      (node (ref "IC3") (pin "1") (pinfunction "GND_1") (pintype "power_in"))
      (node (ref "IC4") (pin "P$3") (pinfunction "GND_P$3") (pintype "power_in"))
      (node (ref "J1") (pin "GND") (pinfunction "GND_GND") (pintype "bidirectional"))
      (node (ref "J1") (pin "SHIELD1") (pinfunction "SHIELD_SHIELD1") (pintype "bidirectional"))
      (node (ref "J1") (pin "SHIELD2") (pinfunction "SHIELD_SHIELD2") (pintype "bidirectional"))
      (node (ref "J1") (pin "SHIELD3") (pinfunction "SHIELD_SHIELD3") (pintype "bidirectional"))
      (node (ref "J1") (pin "SHIELD4") (pinfunction "SHIELD_SHIELD4") (pintype "bidirectional"))
      (node (ref "JP2") (pin "1") (pinfunction "1_1") (pintype "passive"))
      (node (ref "JP4") (pin "1") (pinfunction "1_1") (pintype "passive"))
      (node (ref "JP5") (pin "2") (pinfunction "2_2") (pintype "passive"))
      (node (ref "JP6") (pin "3") (pinfunction "3_3") (pintype "passive"))
      (node (ref "Q2") (pin "2") (pinfunction "S_2") (pintype "passive"))
      (node (ref "Q3") (pin "2") (pinfunction "S_2") (pintype "passive"))
      (node (ref "Q7") (pin "2") (pinfunction "S_2") (pintype "passive"))
      (node (ref "R1") (pin "1") (pinfunction "1_1") (pintype "passive"))
      (node (ref "R13") (pin "1") (pinfunction "1_1") (pintype "passive"))
      (node (ref "R14") (pin "1") (pinfunction "1_1") (pintype "passive"))
      (node (ref "R16") (pin "1") (pinfunction "1_1") (pintype "passive"))
      (node (ref "R25") (pin "1") (pinfunction "1_1") (pintype "passive"))
      (node (ref "R32") (pin "2") (pinfunction "2_2") (pintype "passive"))
      (node (ref "R34") (pin "1") (pinfunction "1_1") (pintype "passive"))
      (node (ref "R40") (pin "2") (pinfunction "2_2") (pintype "passive"))
      (node (ref "R41") (pin "2") (pinfunction "2_2") (pintype "passive"))
      (node (ref "R43") (pin "2") (pinfunction "2_2") (pintype "passive"))
      (node (ref "R5") (pin "2") (pinfunction "2_2") (pintype "passive"))
      (node (ref "R7") (pin "2") (pinfunction "2_2") (pintype "passive"))
      (node (ref "R9") (pin "2") (pinfunction "2_2") (pintype "passive"))
      (node (ref "SW1") (pin "2") (pinfunction "2_2") (pintype "bidirectional"))
      (node (ref "U$2") (pin "11") (pinfunction "FSYNC_11") (pintype "bidirectional"))
      (node (ref "U$2") (pin "18") (pinfunction "GND_18") (pintype "bidirectional"))
      (node (ref "U$2") (pin "20") (pinfunction "RESV2_20") (pintype "bidirectional"))
      (node (ref "U$2") (pin "9") (pinfunction "ADO/SDO_9") (pintype "bidirectional"))
      (node (ref "U1") (pin "P$3") (pinfunction "GND_P$3") (pintype "bidirectional"))
      (node (ref "U2") (pin "4") (pinfunction "GND_4") (pintype "power_in"))
      (node (ref "UC1") (pin "P$12") (pinfunction "VSSA_P$12") (pintype "power_in"))
      (node (ref "UC1") (pin "P$18") (pinfunction "VSS_4_P$18") (pintype "power_in"))
      (node (ref "UC1") (pin "P$31") (pinfunction "VSS_1_P$31") (pintype "power_in"))
      (node (ref "UC1") (pin "P$47") (pinfunction "VSS_2_P$47") (pintype "power_in"))
      (node (ref "UC1") (pin "P$63") (pinfunction "VSS_3_P$63") (pintype "power_in"))
    )
    (net (code "48") (name "Net-(C16-Pad2)") (class "Default")
      (node (ref "C16") (pin "2") (pinfunction "2_2") (pintype "passive"))
      (node (ref "D4") (pin "A") (pinfunction "A_A") (pintype "passive"))
      (node (ref "R41") (pin "1") (pinfunction "1_1") (pintype "passive"))
    )
    (net (code "49") (name "Net-(C22-Pad2)") (class "Default")
      (node (ref "C22") (pin "2") (pinfunction "2_2") (pintype "passive"))
      (node (ref "D3") (pin "A") (pinfunction "A_A") (pintype "passive"))
      (node (ref "R43") (pin "1") (pinfunction "1_1") (pintype "passive"))
    )
    (net (code "50") (name "Net-(IC1-BYP)") (class "Default")
      (node (ref "C5") (pin "1") (pinfunction "1_1") (pintype "passive"))
      (node (ref "IC1") (pin "4") (pinfunction "BYP_4") (pintype "passive"))
    )
    (net (code "51") (name "Net-(IC1-EN)") (class "Default")
      (node (ref "IC1") (pin "3") (pinfunction "EN_3") (pintype "input"))
      (node (ref "IC3") (pin "2") (pinfunction "~{RES}_2") (pintype "output"))
    )
    (net (code "52") (name "Net-(IC2-PROG)") (class "Default")
      (node (ref "IC2") (pin "5") (pinfunction "PROG_5") (pintype "input"))
      (node (ref "R1") (pin "2") (pinfunction "2_2") (pintype "passive"))
    )
    (net (code "53") (name "Net-(IC5-GPA0)") (class "Default")
      (node (ref "IC5") (pin "21") (pinfunction "GPA0_21") (pintype "bidirectional"))
      (node (ref "U$1") (pin "16") (pinfunction "DB7_16") (pintype "bidirectional"))
    )
    (net (code "54") (name "Net-(IC5-GPA1)") (class "Default")
      (node (ref "IC5") (pin "22") (pinfunction "GPA1_22") (pintype "bidirectional"))
      (node (ref "U$1") (pin "15") (pinfunction "DB6_15") (pintype "bidirectional"))
    )
    (net (code "55") (name "Net-(IC5-GPA2)") (class "Default")
      (node (ref "IC5") (pin "23") (pinfunction "GPA2_23") (pintype "bidirectional"))
      (node (ref "U$1") (pin "14") (pinfunction "DB5_14") (pintype "bidirectional"))
    )
    (net (code "56") (name "Net-(IC5-GPA3)") (class "Default")
      (node (ref "IC5") (pin "24") (pinfunction "GPA3_24") (pintype "bidirectional"))
      (node (ref "U$1") (pin "13") (pinfunction "DB4_13") (pintype "bidirectional"))
    )
    (net (code "57") (name "Net-(IC5-GPA4)") (class "Default")
      (node (ref "IC5") (pin "25") (pinfunction "GPA4_25") (pintype "bidirectional"))
      (node (ref "U$1") (pin "12") (pinfunction "DB3_12") (pintype "bidirectional"))
    )
    (net (code "58") (name "Net-(IC5-GPA5)") (class "Default")
      (node (ref "IC5") (pin "26") (pinfunction "GPA5_26") (pintype "bidirectional"))
      (node (ref "U$1") (pin "11") (pinfunction "DB2_11") (pintype "bidirectional"))
    )
    (net (code "59") (name "Net-(IC5-GPA6)") (class "Default")
      (node (ref "IC5") (pin "27") (pinfunction "GPA6_27") (pintype "bidirectional"))
      (node (ref "U$1") (pin "10") (pinfunction "DB1_10") (pintype "bidirectional"))
    )
    (net (code "60") (name "Net-(IC5-GPA7)") (class "Default")
      (node (ref "IC5") (pin "28") (pinfunction "GPA7_28") (pintype "bidirectional"))
      (node (ref "U$1") (pin "9") (pinfunction "DB0_9") (pintype "bidirectional"))
    )
    (net (code "61") (name "Net-(IC5-GPB0)") (class "Default")
      (node (ref "IC5") (pin "1") (pinfunction "GPB0_1") (pintype "bidirectional"))
      (node (ref "U$1") (pin "4") (pinfunction "CSB_4") (pintype "bidirectional"))
    )
    (net (code "62") (name "Net-(IC5-GPB1)") (class "Default")
      (node (ref "IC5") (pin "2") (pinfunction "GPB1_2") (pintype "bidirectional"))
      (node (ref "U$1") (pin "5") (pinfunction "/RES_5") (pintype "bidirectional"))
    )
    (net (code "63") (name "Net-(IC5-GPB2)") (class "Default")
      (node (ref "IC5") (pin "3") (pinfunction "GPB2_3") (pintype "bidirectional"))
      (node (ref "U$1") (pin "6") (pinfunction "A0_6") (pintype "bidirectional"))
    )
    (net (code "64") (name "Net-(IC5-GPB3)") (class "Default")
      (node (ref "IC5") (pin "4") (pinfunction "GPB3_4") (pintype "bidirectional"))
      (node (ref "U$1") (pin "7") (pinfunction "R/W(WR)_7") (pintype "bidirectional"))
    )
    (net (code "65") (name "Net-(IC5-GPB4)") (class "Default")
      (node (ref "IC5") (pin "5") (pinfunction "GPB4_5") (pintype "bidirectional"))
      (node (ref "U$1") (pin "8") (pinfunction "E_RD_8") (pintype "bidirectional"))
    )
    (net (code "66") (name "Net-(IC5-\\~{RESET})") (class "Default")
      (node (ref "IC5") (pin "18") (pinfunction "\\~{RESET}_18") (pintype "input"))
      (node (ref "R19") (pin "2") (pinfunction "2_2") (pintype "passive"))
      (node (ref "R21") (pin "1") (pinfunction "1_1") (pintype "passive"))
    )
    (net (code "67") (name "Net-(J1-PadD+)") (class "Default")
      (node (ref "J1") (pin "D+") (pinfunction "D+_D+") (pintype "bidirectional"))
      (node (ref "R15") (pin "2") (pinfunction "2_2") (pintype "passive"))
      (node (ref "R24") (pin "2") (pinfunction "2_2") (pintype "passive"))
    )
    (net (code "68") (name "Net-(J1-PadD-)") (class "Default")
      (node (ref "J1") (pin "D-") (pinfunction "D-_D-") (pintype "bidirectional"))
      (node (ref "R30") (pin "2") (pinfunction "2_2") (pintype "passive"))
    )
    (net (code "69") (name "Net-(JP3-Pad4)") (class "Default")
      (node (ref "JP3") (pin "4") (pinfunction "4_4") (pintype "passive"))
      (node (ref "R39") (pin "1") (pinfunction "1_1") (pintype "passive"))
    )
    (net (code "70") (name "Net-(OSC2-2)") (class "Default")
      (node (ref "C20") (pin "2") (pinfunction "2_2") (pintype "passive"))
      (node (ref "OSC2") (pin "4") (pinfunction "2_4") (pintype "passive"))
      (node (ref "UC1") (pin "P$4") (pinfunction "PC15/OSC_OUT_P$4") (pintype "bidirectional"))
    )
    (net (code "71") (name "Net-(Q1-D)") (class "Default")
      (node (ref "Q1") (pin "3") (pinfunction "D_3") (pintype "passive"))
      (node (ref "R6") (pin "1") (pinfunction "1_1") (pintype "passive"))
    )
    (net (code "72") (name "Net-(Q1-G)") (class "Default")
      (node (ref "Q1") (pin "1") (pinfunction "G_1") (pintype "passive"))
      (node (ref "Q2") (pin "3") (pinfunction "D_3") (pintype "passive"))
      (node (ref "R4") (pin "2") (pinfunction "2_2") (pintype "passive"))
    )
    (net (code "73") (name "Net-(Q1-S)") (class "Default")
      (node (ref "Q1") (pin "2") (pinfunction "S_2") (pintype "passive"))
      (node (ref "R22") (pin "2") (pinfunction "2_2") (pintype "passive"))
      (node (ref "R4") (pin "1") (pinfunction "1_1") (pintype "passive"))
    )
    (net (code "74") (name "Net-(Q3-D)") (class "Default")
      (node (ref "Q3") (pin "3") (pinfunction "D_3") (pintype "passive"))
      (node (ref "Q5") (pin "3") (pinfunction "D_3") (pintype "passive"))
      (node (ref "Q6") (pin "1") (pinfunction "G_1") (pintype "passive"))
      (node (ref "R11") (pin "1") (pinfunction "1_1") (pintype "passive"))
      (node (ref "SP1") (pin "+") (pinfunction "2_+") (pintype "passive"))
    )
    (net (code "75") (name "Net-(Q3-G)") (class "Default")
      (node (ref "Q3") (pin "1") (pinfunction "G_1") (pintype "passive"))
      (node (ref "R25") (pin "2") (pinfunction "2_2") (pintype "passive"))
      (node (ref "R27") (pin "2") (pinfunction "2_2") (pintype "passive"))
    )
    (net (code "76") (name "Net-(Q4-D)") (class "Default")
      (node (ref "Q4") (pin "3") (pinfunction "D_3") (pintype "passive"))
      (node (ref "U$1") (pin "K") (pinfunction "K_K") (pintype "bidirectional"))
    )
    (net (code "77") (name "Net-(Q5-G)") (class "Default")
      (node (ref "Q5") (pin "1") (pinfunction "G_1") (pintype "passive"))
      (node (ref "Q6") (pin "3") (pinfunction "D_3") (pintype "passive"))
      (node (ref "Q7") (pin "3") (pinfunction "D_3") (pintype "passive"))
      (node (ref "R12") (pin "1") (pinfunction "1_1") (pintype "passive"))
      (node (ref "SP1") (pin "-") (pinfunction "1_-") (pintype "passive"))
    )
    (net (code "78") (name "Net-(Q5-S)") (class "Default")
      (node (ref "Q5") (pin "2") (pinfunction "S_2") (pintype "passive"))
      (node (ref "Q6") (pin "2") (pinfunction "S_2") (pintype "passive"))
      (node (ref "R11") (pin "2") (pinfunction "2_2") (pintype "passive"))
      (node (ref "R12") (pin "2") (pinfunction "2_2") (pintype "passive"))
      (node (ref "R2") (pin "1") (pinfunction "1_1") (pintype "passive"))
    )
    (net (code "79") (name "Net-(Q7-G)") (class "Default")
      (node (ref "Q7") (pin "1") (pinfunction "G_1") (pintype "passive"))
      (node (ref "R13") (pin "2") (pinfunction "2_2") (pintype "passive"))
      (node (ref "R29") (pin "1") (pinfunction "1_1") (pintype "passive"))
    )
    (net (code "80") (name "Net-(Q9-D)") (class "Default")
      (node (ref "Q9") (pin "3") (pinfunction "D_3") (pintype "passive"))
      (node (ref "U1") (pin "P$1") (pinfunction "VCC_P$1") (pintype "bidirectional"))
    )
    (net (code "81") (name "Net-(Q9-G)") (class "Default")
      (node (ref "Q9") (pin "1") (pinfunction "G_1") (pintype "passive"))
      (node (ref "R10") (pin "1") (pinfunction "1_1") (pintype "passive"))
      (node (ref "R23") (pin "1") (pinfunction "1_1") (pintype "passive"))
    )
    (net (code "82") (name "Net-(Q10-D)") (class "Default")
      (node (ref "Q10") (pin "3") (pinfunction "D_3") (pintype "passive"))
      (node (ref "R15") (pin "1") (pinfunction "1_1") (pintype "passive"))
    )
    (net (code "83") (name "Net-(Q10-G)") (class "Default")
      (node (ref "Q10") (pin "1") (pinfunction "G_1") (pintype "passive"))
      (node (ref "R37") (pin "1") (pinfunction "1_1") (pintype "passive"))
      (node (ref "R38") (pin "1") (pinfunction "1_1") (pintype "passive"))
    )
    (net (code "84") (name "Net-(R16-Pad2)") (class "Default")
      (node (ref "R16") (pin "2") (pinfunction "2_2") (pintype "passive"))
      (node (ref "R26") (pin "1") (pinfunction "1_1") (pintype "passive"))
    )
    (net (code "85") (name "Net-(R36-Pad2)") (class "Default")
      (node (ref "R36") (pin "2") (pinfunction "2_2") (pintype "passive"))
      (node (ref "R6") (pin "2") (pinfunction "2_2") (pintype "passive"))
      (node (ref "R7") (pin "1") (pinfunction "1_1") (pintype "passive"))
    )
    (net (code "86") (name "Net-(U$1-PS1)") (class "Default")
      (node (ref "R20") (pin "2") (pinfunction "2_2") (pintype "passive"))
      (node (ref "U$1") (pin "2") (pinfunction "PS1_2") (pintype "bidirectional"))
      (node (ref "U$1") (pin "3") (pinfunction "PS2_3") (pintype "bidirectional"))
    )
    (net (code "87") (name "Net-(U$1-V1)") (class "Default")
      (node (ref "C6") (pin "2") (pinfunction "2_2") (pintype "passive"))
      (node (ref "U$1") (pin "30") (pinfunction "V1_30") (pintype "bidirectional"))
    )
    (net (code "88") (name "Net-(U$1-V2)") (class "Default")
      (node (ref "C23") (pin "2") (pinfunction "2_2") (pintype "passive"))
      (node (ref "U$1") (pin "29") (pinfunction "V2_29") (pintype "bidirectional"))
    )
    (net (code "89") (name "Net-(U$1-V3)") (class "Default")
      (node (ref "C24") (pin "2") (pinfunction "2_2") (pintype "passive"))
      (node (ref "U$1") (pin "28") (pinfunction "V3_28") (pintype "bidirectional"))
    )
    (net (code "90") (name "Net-(U$1-V4)") (class "Default")
      (node (ref "C25") (pin "2") (pinfunction "2_2") (pintype "passive"))
      (node (ref "U$1") (pin "27") (pinfunction "V4_27") (pintype "bidirectional"))
    )
    (net (code "91") (name "Net-(U$1-VOUT)") (class "Default")
      (node (ref "C26") (pin "2") (pinfunction "2_2") (pintype "passive"))
      (node (ref "U$1") (pin "25") (pinfunction "VOUT_25") (pintype "bidirectional"))
    )
    (net (code "92") (name "Net-(U$2-REGOUT)") (class "Default")
      (node (ref "C29") (pin "1") (pinfunction "1_1") (pintype "passive"))
      (node (ref "U$2") (pin "10") (pinfunction "REGOUT_10") (pintype "bidirectional"))
    )
    (net (code "93") (name "Net-(U1-TX)") (class "Default")
      (node (ref "R3") (pin "1") (pinfunction "1_1") (pintype "passive"))
      (node (ref "U1") (pin "P$9") (pinfunction "TX_P$9") (pintype "bidirectional"))
    )
    (net (code "94") (name "Net-(U2-VCC)") (class "Default")
      (node (ref "C17") (pin "2") (pinfunction "2_2") (pintype "passive"))
      (node (ref "R28") (pin "2") (pinfunction "2_2") (pintype "passive"))
      (node (ref "R31") (pin "2") (pinfunction "2_2") (pintype "passive"))
      (node (ref "R33") (pin "2") (pinfunction "2_2") (pintype "passive"))
      (node (ref "R35") (pin "1") (pinfunction "1_1") (pintype "passive"))
      (node (ref "U2") (pin "8") (pinfunction "VCC_8") (pintype "power_in"))
    )
    (net (code "95") (name "Net-(U2-~{HOLD})") (class "Default")
      (node (ref "R33") (pin "1") (pinfunction "1_1") (pintype "passive"))
      (node (ref "U2") (pin "7") (pinfunction "~{HOLD}_7") (pintype "input"))
    )
    (net (code "96") (name "Net-(U2-~{WP})") (class "Default")
      (node (ref "R31") (pin "1") (pinfunction "1_1") (pintype "passive"))
      (node (ref "U2") (pin "3") (pinfunction "~{WP}_3") (pintype "input"))
    )
    (net (code "97") (name "Net-(UC1-BOOT0)") (class "Default")
      (node (ref "R14") (pin "2") (pinfunction "2_2") (pintype "passive"))
      (node (ref "UC1") (pin "P$60") (pinfunction "BOOT0_P$60") (pintype "bidirectional"))
    )
    (net (code "98") (name "Net-(UC1-NRST)") (class "Default")
      (node (ref "C8") (pin "2") (pinfunction "2_2") (pintype "passive"))
      (node (ref "SW1") (pin "3") (pinfunction "3_3") (pintype "bidirectional"))
      (node (ref "UC1") (pin "P$7") (pinfunction "NRST_P$7") (pintype "bidirectional"))
    )
    (net (code "99") (name "Net-(UC1-PA13{slash}JTMS-SWDAT)") (class "Default")
      (node (ref "JP4") (pin "3") (pinfunction "3_3") (pintype "passive"))
      (node (ref "UC1") (pin "P$46") (pinfunction "PA13/JTMS-SWDAT_P$46") (pintype "bidirectional"))
    )
    (net (code "100") (name "Net-(UC1-PA14{slash}JTCK-SWCLK)") (class "Default")
      (node (ref "JP4") (pin "2") (pinfunction "2_2") (pintype "passive"))
      (node (ref "UC1") (pin "P$49") (pinfunction "PA14/JTCK-SWCLK_P$49") (pintype "bidirectional"))
    )
    (net (code "101") (name "Net-(UC1-PB2{slash}BOOT1)") (class "Default")
      (node (ref "R26") (pin "2") (pinfunction "2_2") (pintype "passive"))
      (node (ref "UC1") (pin "P$28") (pinfunction "PB2/BOOT1_P$28") (pintype "bidirectional"))
    )
    (net (code "102") (name "Net-(UC1-PB10{slash}I2C2_SCL{slash}USART3_TX)") (class "Default")
      (node (ref "JP6") (pin "1") (pinfunction "1_1") (pintype "passive"))
      (node (ref "UC1") (pin "P$29") (pinfunction "PB10/I2C2_SCL/USART3_TX_P$29") (pintype "bidirectional"))
    )
    (net (code "103") (name "Net-(UC1-PB11{slash}I2C2_SDA{slash}USART3_RX)") (class "Default")
      (node (ref "JP6") (pin "2") (pinfunction "2_2") (pintype "passive"))
      (node (ref "UC1") (pin "P$30") (pinfunction "PB11/I2C2_SDA/USART3_RX_P$30") (pintype "bidirectional"))
    )
    (net (code "104") (name "Net-(UC1-PC14{slash}OSC32_IN)") (class "Default")
      (node (ref "C19") (pin "2") (pinfunction "2_2") (pintype "passive"))
      (node (ref "OSC2") (pin "1") (pinfunction "1_1") (pintype "passive"))
      (node (ref "UC1") (pin "P$3") (pinfunction "PC14/OSC32_IN_P$3") (pintype "bidirectional"))
    )
    (net (code "105") (name "Net-(UC1-PD0{slash}OSC_IN)") (class "Default")
      (node (ref "C12") (pin "2") (pinfunction "2_2") (pintype "passive"))
      (node (ref "OSC") (pin "2") (pinfunction "2_2") (pintype "passive"))
      (node (ref "UC1") (pin "P$5") (pinfunction "PD0/OSC_IN_P$5") (pintype "bidirectional"))
    )
    (net (code "106") (name "Net-(UC1-PD1{slash}OSC_OUT)") (class "Default")
      (node (ref "C13") (pin "2") (pinfunction "2_2") (pintype "passive"))
      (node (ref "OSC") (pin "1") (pinfunction "1_1") (pintype "passive"))
      (node (ref "UC1") (pin "P$6") (pinfunction "PD1/OSC_OUT_P$6") (pintype "bidirectional"))
    )
    (net (code "107") (name "VCC") (class "Default")
      (node (ref "C10") (pin "2") (pinfunction "2_2") (pintype "passive"))
      (node (ref "C14") (pin "2") (pinfunction "2_2") (pintype "passive"))
      (node (ref "C21") (pin "2") (pinfunction "2_2") (pintype "passive"))
      (node (ref "C3") (pin "1") (pinfunction "1_1") (pintype "passive"))
      (node (ref "C4") (pin "1") (pinfunction "1_1") (pintype "passive"))
      (node (ref "C9") (pin "2") (pinfunction "2_2") (pintype "passive"))
      (node (ref "IC1") (pin "5") (pinfunction "OUT_5") (pintype "output"))
      (node (ref "JP2") (pin "2") (pinfunction "2_2") (pintype "passive"))
      (node (ref "Q10") (pin "2") (pinfunction "S_2") (pintype "passive"))
      (node (ref "Q9") (pin "2") (pinfunction "S_2") (pintype "passive"))
      (node (ref "R10") (pin "2") (pinfunction "2_2") (pintype "passive"))
      (node (ref "R35") (pin "2") (pinfunction "2_2") (pintype "passive"))
      (node (ref "R37") (pin "2") (pinfunction "2_2") (pintype "passive"))
      (node (ref "R39") (pin "2") (pinfunction "2_2") (pintype "passive"))
      (node (ref "U1") (pin "P$4") (pinfunction "VBACKUP_P$4") (pintype "bidirectional"))
      (node (ref "UC1") (pin "P$1") (pinfunction "VBAT_P$1") (pintype "power_in"))
      (node (ref "UC1") (pin "P$13") (pinfunction "VDDA_P$13") (pintype "power_in"))
      (node (ref "UC1") (pin "P$19") (pinfunction "VDD_4_P$19") (pintype "power_in"))
      (node (ref "UC1") (pin "P$32") (pinfunction "VDD_1_P$32") (pintype "power_in"))
      (node (ref "UC1") (pin "P$48") (pinfunction "VDD_2_P$48") (pintype "power_in"))
      (node (ref "UC1") (pin "P$64") (pinfunction "VDD_3_P$64") (pintype "power_in"))
    )
    (net (code "108") (name "unconnected-(IC4-SDO-PadP$6)") (class "Default")
      (node (ref "IC4") (pin "P$6") (pinfunction "SDO_P$6") (pintype "output"))
    )
    (net (code "109") (name "unconnected-(IC5-GPB5-Pad6)") (class "Default")
      (node (ref "IC5") (pin "6") (pinfunction "GPB5_6") (pintype "bidirectional"))
    )
    (net (code "110") (name "unconnected-(IC5-GPB6-Pad7)") (class "Default")
      (node (ref "IC5") (pin "7") (pinfunction "GPB6_7") (pintype "bidirectional"))
    )
    (net (code "111") (name "unconnected-(IC5-GPB7-Pad8)") (class "Default")
      (node (ref "IC5") (pin "8") (pinfunction "GPB7_8") (pintype "bidirectional"))
    )
    (net (code "112") (name "unconnected-(IC5-INTA-Pad20)") (class "Default")
      (node (ref "IC5") (pin "20") (pinfunction "INTA_20") (pintype "output"))
    )
    (net (code "113") (name "unconnected-(IC5-INTB-Pad19)") (class "Default")
      (node (ref "IC5") (pin "19") (pinfunction "INTB_19") (pintype "output"))
    )
    (net (code "114") (name "unconnected-(J1-USBID-PadID)") (class "Default")
      (node (ref "J1") (pin "ID") (pinfunction "USBID_ID") (pintype "bidirectional"))
    )
    (net (code "115") (name "unconnected-(JP1-Pad1)") (class "Default")
      (node (ref "JP1") (pin "1") (pinfunction "1_1") (pintype "passive"))
    )
    (net (code "116") (name "unconnected-(SW1-Pad1)") (class "Default")
      (node (ref "SW1") (pin "1") (pinfunction "1_1") (pintype "bidirectional"))
    )
    (net (code "117") (name "unconnected-(SW1-Pad4)") (class "Default")
      (node (ref "SW1") (pin "4") (pinfunction "4_4") (pintype "bidirectional"))
    )
    (net (code "118") (name "unconnected-(U$1-V0-Pad31)") (class "Default")
      (node (ref "U$1") (pin "31") (pinfunction "V0_31") (pintype "bidirectional"))
    )
    (net (code "119") (name "unconnected-(U$2-INT-Pad12)") (class "Default")
      (node (ref "U$2") (pin "12") (pinfunction "INT_12") (pintype "bidirectional"))
    )
    (net (code "120") (name "unconnected-(U$2-NC1-Pad2)") (class "Default")
      (node (ref "U$2") (pin "2") (pinfunction "NC1_2") (pintype "bidirectional"))
    )
    (net (code "121") (name "unconnected-(U$2-NC2-Pad3)") (class "Default")
      (node (ref "U$2") (pin "3") (pinfunction "NC2_3") (pintype "bidirectional"))
    )
    (net (code "122") (name "unconnected-(U$2-NC3-Pad4)") (class "Default")
      (node (ref "U$2") (pin "4") (pinfunction "NC3_4") (pintype "bidirectional"))
    )
    (net (code "123") (name "unconnected-(U$2-NC4-Pad5)") (class "Default")
      (node (ref "U$2") (pin "5") (pinfunction "NC4_5") (pintype "bidirectional"))
    )
    (net (code "124") (name "unconnected-(U$2-NC5-Pad6)") (class "Default")
      (node (ref "U$2") (pin "6") (pinfunction "NC5_6") (pintype "bidirectional"))
    )
    (net (code "125") (name "unconnected-(U$2-NC6-Pad14)") (class "Default")
      (node (ref "U$2") (pin "14") (pinfunction "NC6_14") (pintype "bidirectional"))
    )
    (net (code "126") (name "unconnected-(U$2-NC7-Pad15)") (class "Default")
      (node (ref "U$2") (pin "15") (pinfunction "NC7_15") (pintype "bidirectional"))
    )
    (net (code "127") (name "unconnected-(U$2-NC8-Pad16)") (class "Default")
      (node (ref "U$2") (pin "16") (pinfunction "NC8_16") (pintype "bidirectional"))
    )
    (net (code "128") (name "unconnected-(U$2-NC9-Pad17)") (class "Default")
      (node (ref "U$2") (pin "17") (pinfunction "NC9_17") (pintype "bidirectional"))
    )
    (net (code "129") (name "unconnected-(U$2-PAD-Pad25)") (class "Default")
      (node (ref "U$2") (pin "25") (pinfunction "PAD_25") (pintype "bidirectional"))
    )
    (net (code "130") (name "unconnected-(U$2-RESV1-Pad19)") (class "Default")
      (node (ref "U$2") (pin "19") (pinfunction "RESV1_19") (pintype "bidirectional"))
    )
    (net (code "131") (name "unconnected-(U1-1PPS-PadP$6)") (class "Default")
      (node (ref "U1") (pin "P$6") (pinfunction "1PPS_P$6") (pintype "bidirectional"))
    )
    (net (code "132") (name "unconnected-(U1-GND-PadP$8)") (class "Default")
      (node (ref "U1") (pin "P$8") (pinfunction "GND_P$8") (pintype "bidirectional"))
    )
    (net (code "133") (name "unconnected-(U1-NC-PadP$2)") (class "Default")
      (node (ref "U1") (pin "P$2") (pinfunction "NC_P$2") (pintype "bidirectional"))
    )
    (net (code "134") (name "unconnected-(U1-NC-PadP$7)") (class "Default")
      (node (ref "U1") (pin "P$7") (pinfunction "NC_P$7") (pintype "bidirectional"))
    )
    (net (code "135") (name "unconnected-(U1-NC-PadP$11)") (class "Default")
      (node (ref "U1") (pin "P$11") (pinfunction "NC_P$11") (pintype "bidirectional"))
    )
    (net (code "136") (name "unconnected-(U1-NC-PadP$12)") (class "Default")
      (node (ref "U1") (pin "P$12") (pinfunction "NC_P$12") (pintype "bidirectional"))
    )
    (net (code "137") (name "unconnected-(U1-NC-PadP$13)") (class "Default")
      (node (ref "U1") (pin "P$13") (pinfunction "NC_P$13") (pintype "bidirectional"))
    )
    (net (code "138") (name "unconnected-(UC1-PA15{slash}JTDI-PadP$50)") (class "Default")
      (node (ref "UC1") (pin "P$50") (pinfunction "PA15/JTDI_P$50") (pintype "bidirectional"))
    )
    (net (code "139") (name "unconnected-(UC1-PB3{slash}JTDO-PadP$55)") (class "Default")
      (node (ref "UC1") (pin "P$55") (pinfunction "PB3/JTDO_P$55") (pintype "bidirectional"))
    )
    (net (code "140") (name "unconnected-(UC1-PB4{slash}JTRST-PadP$56)") (class "Default")
      (node (ref "UC1") (pin "P$56") (pinfunction "PB4/JTRST_P$56") (pintype "bidirectional"))
    )
    (net (code "141") (name "unconnected-(UC1-PB8{slash}TIM4_CH3-PadP$61)") (class "Default")
      (node (ref "UC1") (pin "P$61") (pinfunction "PB8/TIM4_CH3_P$61") (pintype "bidirectional"))
    )
    (net (code "142") (name "unconnected-(UC1-PB9{slash}TIM4_CH4-PadP$62)") (class "Default")
      (node (ref "UC1") (pin "P$62") (pinfunction "PB9/TIM4_CH4_P$62") (pintype "bidirectional"))
    )
    (net (code "143") (name "unconnected-(UC1-PC5{slash}ADC15-PadP$25)") (class "Default")
      (node (ref "UC1") (pin "P$25") (pinfunction "PC5/ADC15_P$25") (pintype "bidirectional"))
    )
    (net (code "144") (name "unconnected-(UC1-PC8-PadP$39)") (class "Default")
      (node (ref "UC1") (pin "P$39") (pinfunction "PC8_P$39") (pintype "bidirectional"))
    )
    (net (code "145") (name "unconnected-(UC1-PC9-PadP$40)") (class "Default")
      (node (ref "UC1") (pin "P$40") (pinfunction "PC9_P$40") (pintype "bidirectional"))
    )
    (net (code "146") (name "unconnected-(UC1-PC11-PadP$52)") (class "Default")
      (node (ref "UC1") (pin "P$52") (pinfunction "PC11_P$52") (pintype "bidirectional"))
    )
    (net (code "147") (name "unconnected-(UC1-PC12-PadP$53)") (class "Default")
      (node (ref "UC1") (pin "P$53") (pinfunction "PC12_P$53") (pintype "bidirectional"))
    )
    (net (code "148") (name "unconnected-(UC1-PC13-TAMPER-RTC-PadP$2)") (class "Default")
      (node (ref "UC1") (pin "P$2") (pinfunction "PC13-TAMPER-RTC_P$2") (pintype "bidirectional"))
    )
    (net (code "149") (name "unconnected-(UC1-PD2{slash}TIM3-ETR-PadP$54)") (class "Default")
      (node (ref "UC1") (pin "P$54") (pinfunction "PD2/TIM3-ETR_P$54") (pintype "bidirectional"))
    )
  )
)
